# POW_Schematic1.net
KiCad netlist of a schematic drawn in Altium Designer
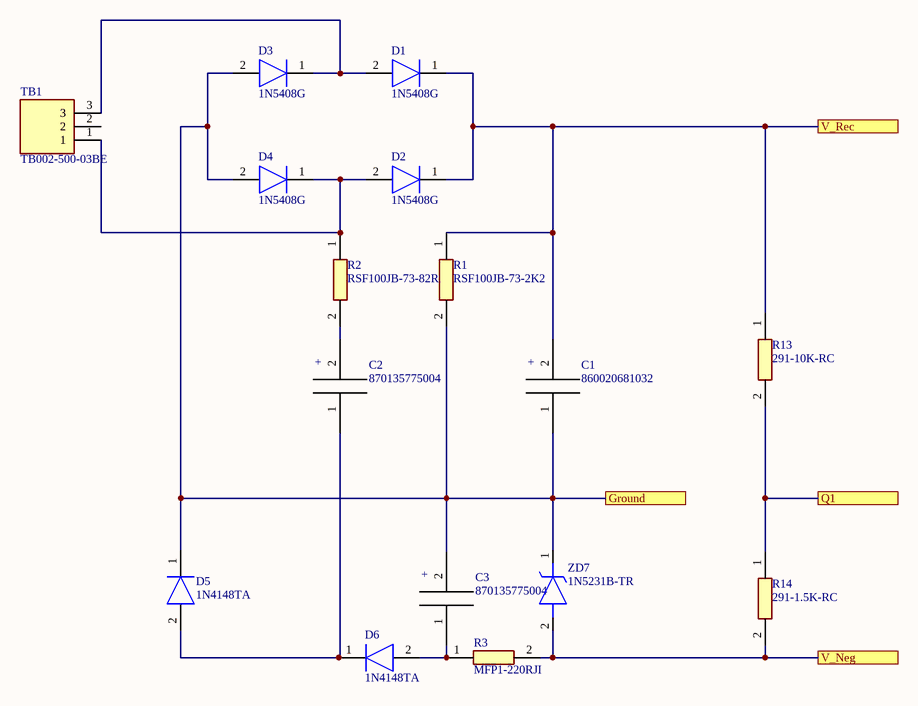
[diagram p0: POW_Schematic1.SchDoc]

(export (version "E")
  (design (tool "Eeschema 10.0.6"))
  (components
    (comp (ref "C1")
      (value "860020681032")
      (footprint "860020681032")
      (description "Capacitor 3300uF 50V")
      (libsource (lib "Schlib_POW_HugoHamblok") (part "860020681032"))
    )
    (comp (ref "C2")
      (value "870135775004")
      (footprint "870135775004")
      (description "Capacitor 47uF 50V")
      (libsource (lib "Schlib_POW_HugoHamblok") (part "870135775004"))
    )
    (comp (ref "C3")
      (value "870135775004")
      (footprint "870135775004")
      (description "Capacitor 47uF 50V")
      (libsource (lib "Schlib_POW_HugoHamblok") (part "870135775004"))
    )
    (comp (ref "D1")
      (value "1N5408G")
      (footprint "DIOAD2860W130L840D505")
      (description "Diode")
      (fields (field (name "MOUSER PART NUMBER") "863-1N5408G") (field (name "RS PART NUMBER") "7743344P"))
      (libsource (lib "Schlib_POW_HugoHamblok") (part "1N5408G"))
    )
    (comp (ref "D2")
      (value "1N5408G")
      (footprint "DIOAD2860W130L840D505")
      (description "Diode")
      (fields (field (name "MOUSER PART NUMBER") "863-1N5408G") (field (name "RS PART NUMBER") "7743344P"))
      (libsource (lib "Schlib_POW_HugoHamblok") (part "1N5408G"))
    )
    (comp (ref "D3")
      (value "1N5408G")
      (footprint "DIOAD2860W130L840D505")
      (description "Diode")
      (fields (field (name "MOUSER PART NUMBER") "863-1N5408G") (field (name "RS PART NUMBER") "7743344P"))
      (libsource (lib "Schlib_POW_HugoHamblok") (part "1N5408G"))
    )
    (comp (ref "D4")
      (value "1N5408G")
      (footprint "DIOAD2860W130L840D505")
      (description "Diode")
      (fields (field (name "MOUSER PART NUMBER") "863-1N5408G") (field (name "RS PART NUMBER") "7743344P"))
      (libsource (lib "Schlib_POW_HugoHamblok") (part "1N5408G"))
    )
    (comp (ref "D5")
      (value "1N4148TA")
      (footprint "DIOAD1068W53L380D172")
      (description "Diode")
      (fields (field (name "MOUSER PART NUMBER") "512-1N4148TA") (field (name "RS PART NUMBER") "7390290P"))
      (libsource (lib "Schlib_POW_HugoHamblok") (part "1N4148TA"))
    )
    (comp (ref "D6")
      (value "1N4148TA")
      (footprint "DIOAD1068W53L380D172")
      (description "Diode")
      (fields (field (name "MOUSER PART NUMBER") "512-1N4148TA") (field (name "RS PART NUMBER") "7390290P"))
      (libsource (lib "Schlib_POW_HugoHamblok") (part "1N4148TA"))
    )
    (comp (ref "R1")
      (value "RSF100JB-73-2K2")
      (footprint "RSF100 Style Footprint")
      (description "Resistor 1W 2.2K Ohm 5%")
      (fields (field (name "MOUSER PART NUMBER") "603-RSF100JB-73-2K2"))
      (libsource (lib "Schlib_POW_HugoHamblok") (part "RSF100JB-73-2K2"))
    )
    (comp (ref "R2")
      (value "RSF100JB-73-82R")
      (footprint "RSF100 Style Footprint")
      (description "Resistor 1W 82 Ohm 5%")
      (libsource (lib "Schlib_POW_HugoHamblok") (part "RSF100JB-73-82R"))
    )
    (comp (ref "R3")
      (value "MFP1-220RJI")
      (footprint "MFP1-220RJI")
      (description "Resistor 220 ohm 5% 1W")
      (libsource (lib "Schlib_POW_HugoHamblok") (part "MFP1-220RJI"))
    )
    (comp (ref "R13")
      (value "291-10K-RC")
      (footprint "291-XXX-RC-Type")
      (libsource (lib "Schlib_POW_HugoHamblok") (part "291-10K-RC"))
    )
    (comp (ref "R14")
      (value "291-1.5K-RC")
      (footprint "291-XXX-RC-Type")
      (libsource (lib "Schlib_POW_HugoHamblok") (part "291-1.5K-RC"))
    )
    (comp (ref "TB1")
      (value "TB002-500-03BE")
      (footprint "SHDR3W100P0X500_1X3_1500X760X1000P")
      (description "Connector")
      (fields (field (name "MOUSER PART NUMBER") "490-TB002-500-03BE"))
      (libsource (lib "Schlib_POW_HugoHamblok") (part "TB002-500-03BE"))
    )
    (comp (ref "ZD7")
      (value "1N5231B-TR")
      (footprint "DIOAD990W55L350D160")
      (description "Zener Diode")
      (fields (field (name "MOUSER PART NUMBER") "78-1N5231B") (field (name "RS PART NUMBER") "8115967P"))
      (libsource (lib "Schlib_POW_HugoHamblok") (part "1N5231B-TR"))
    )
  )
  (nets
    (net (code "1") (name "/Ground") (class "Default")
      (node (ref "C1") (pin "1") (pintype "passive"))
      (node (ref "C3") (pin "2") (pintype "passive"))
      (node (ref "D3") (pin "2") (pinfunction "A_2") (pintype "passive"))
      (node (ref "D4") (pin "2") (pinfunction "A_2") (pintype "passive"))
      (node (ref "D5") (pin "1") (pinfunction "K_1") (pintype "passive"))
      (node (ref "R1") (pin "2") (pinfunction "2_2") (pintype "passive"))
      (node (ref "ZD7") (pin "1") (pinfunction "K_1") (pintype "passive"))
    )
    (net (code "2") (name "/Q1") (class "Default")
      (node (ref "R13") (pin "2") (pinfunction "2_2") (pintype "passive"))
      (node (ref "R14") (pin "1") (pinfunction "1_1") (pintype "passive"))
    )
    (net (code "3") (name "/V_Neg") (class "Default")
      (node (ref "R14") (pin "2") (pinfunction "2_2") (pintype "passive"))
      (node (ref "R3") (pin "2") (pinfunction "2_2") (pintype "passive"))
      (node (ref "ZD7") (pin "2") (pinfunction "A_2") (pintype "passive"))
    )
    (net (code "4") (name "/V_Rec") (class "Default")
      (node (ref "C1") (pin "2") (pintype "passive"))
      (node (ref "D1") (pin "1") (pinfunction "K_1") (pintype "passive"))
      (node (ref "D2") (pin "1") (pinfunction "K_1") (pintype "passive"))
      (node (ref "R1") (pin "1") (pinfunction "1_1") (pintype "passive"))
      (node (ref "R13") (pin "1") (pinfunction "1_1") (pintype "passive"))
    )
    (net (code "5") (name "Net-(C2-Pad2)") (class "Default")
      (node (ref "C2") (pin "2") (pintype "passive"))
      (node (ref "R2") (pin "2") (pinfunction "2_2") (pintype "passive"))
    )
    (net (code "6") (name "Net-(D1-A)") (class "Default")
      (node (ref "D1") (pin "2") (pinfunction "A_2") (pintype "passive"))
      (node (ref "D3") (pin "1") (pinfunction "K_1") (pintype "passive"))
      (node (ref "TB1") (pin "3") (pinfunction "3_3") (pintype "passive"))
    )
    (net (code "7") (name "Net-(D2-A)") (class "Default")
      (node (ref "D2") (pin "2") (pinfunction "A_2") (pintype "passive"))
      (node (ref "D4") (pin "1") (pinfunction "K_1") (pintype "passive"))
      (node (ref "R2") (pin "1") (pinfunction "1_1") (pintype "passive"))
      (node (ref "TB1") (pin "1") (pinfunction "1_1") (pintype "passive"))
    )
    (net (code "8") (name "Net-(D5-A)") (class "Default")
      (node (ref "C2") (pin "1") (pintype "passive"))
      (node (ref "D5") (pin "2") (pinfunction "A_2") (pintype "passive"))
      (node (ref "D6") (pin "1") (pinfunction "K_1") (pintype "passive"))
    )
    (net (code "9") (name "Net-(D6-A)") (class "Default")
      (node (ref "C3") (pin "1") (pintype "passive"))
      (node (ref "D6") (pin "2") (pinfunction "A_2") (pintype "passive"))
      (node (ref "R3") (pin "1") (pinfunction "1_1") (pintype "passive"))
    )
    (net (code "10") (name "unconnected-(TB1-Pad2)") (class "Default")
      (node (ref "TB1") (pin "2") (pinfunction "2_2") (pintype "passive"))
    )
  )
)
